# Schematic.net
KiCad netlist of a schematic drawn in Altium Designer
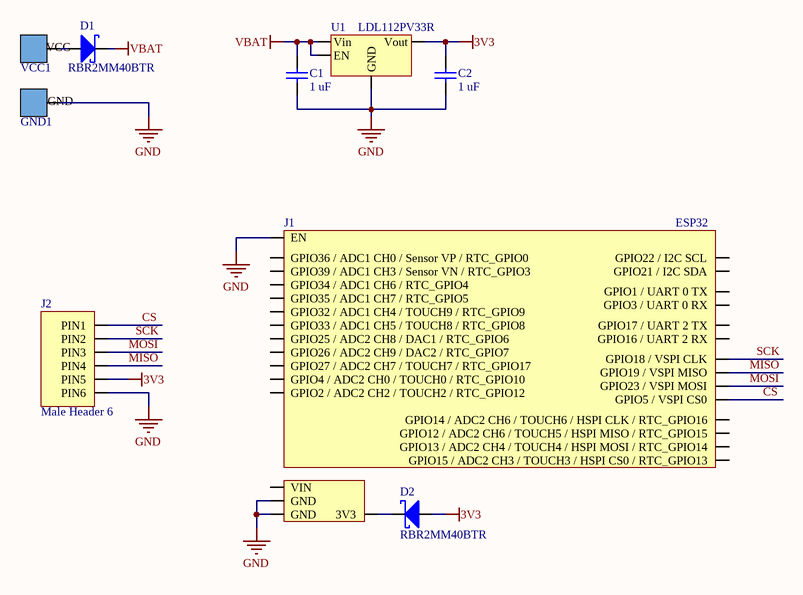
[diagram p0: Schematic.SchDoc]

(export (version "E")
  (design (tool "Eeschema 10.0.6"))
  (components
    (comp (ref "C1")
      (value "1 uF")
      (footprint "C0603")
      (description "CAP CER 1uF 35V X5R 0603")
      (fields
        (field (name "MANUFACTURER") "TAIYO YUDEN")
        (field (name "PART NUMBER") "GMK107BJ105KAHT")
        (field (name "LIBRARY CONTROL - PERSON THAT CHECKED FOOTPRINT") "Nikaum")
        (field (name "LIBRARY CONTROL - PERSON THAT CHECKED SCHEMATIC") "Nikaum")
        (field (name "LIBRARY CONTROL - PERSON THAT DID THE LAST UPDATE FOOTPRINT") "Nikaum")
        (field (name "LIBRARY CONTROL - PERSON THAT DID THE LAST UPDATE SCHEMATIC") "Nikaum")
      )
      (libsource (lib "Uai!Tecas") (part "GMK107BJ105KAHT"))
    )
    (comp (ref "C2")
      (value "1 uF")
      (footprint "C0603")
      (description "CAP CER 1uF 35V X5R 0603")
      (fields
        (field (name "MANUFACTURER") "TAIYO YUDEN")
        (field (name "PART NUMBER") "GMK107BJ105KAHT")
        (field (name "LIBRARY CONTROL - PERSON THAT CHECKED FOOTPRINT") "Nikaum")
        (field (name "LIBRARY CONTROL - PERSON THAT CHECKED SCHEMATIC") "Nikaum")
        (field (name "LIBRARY CONTROL - PERSON THAT DID THE LAST UPDATE FOOTPRINT") "Nikaum")
        (field (name "LIBRARY CONTROL - PERSON THAT DID THE LAST UPDATE SCHEMATIC") "Nikaum")
      )
      (libsource (lib "Uai!Tecas") (part "GMK107BJ105KAHT"))
    )
    (comp (ref "D1")
      (value "RBR2MM40BTR")
      (footprint "DIODO_SOD-123FL-2")
      (description "DIODE SCHOTTKY 40V 2A SOD-123FL-2")
      (fields
        (field (name "MANUFACTURER") "ROHM Semiconductor")
        (field (name "LIBRARY CONTROL - PERSON THAT DID THE LAST UPDATE SCHEMATIC") "Maria Laura")
      )
      (libsource (lib "Uai!Tecas") (part "RBR2MM40BTR"))
    )
    (comp (ref "D2")
      (value "RBR2MM40BTR")
      (footprint "DIODO_SOD-123FL-2")
      (description "DIODE SCHOTTKY 40V 2A SOD-123FL-2")
      (fields
        (field (name "MANUFACTURER") "ROHM Semiconductor")
        (field (name "LIBRARY CONTROL - PERSON THAT DID THE LAST UPDATE SCHEMATIC") "Maria Laura")
      )
      (libsource (lib "Uai!Tecas") (part "RBR2MM40BTR"))
    )
    (comp (ref "GND1")
      (value "Ground Pad")
      (footprint "PAD_ALIMENTAÇÃO_MINI")
      (description "GND PAD MINI SUMÔ")
      (libsource (lib "Uai!Tecas") (part "Ground Pad Mini Sumô"))
    )
    (comp (ref "J1")
      (value "ESP32")
      (footprint "Modulo ESP32")
      (description "Header Modulo ESP32")
      (fields
        (field (name "LIBRARY CONTROL - CHECKED FOOTPRINT") "Nikaum")
        (field (name "LIBRARY CONTROL - CHECKED SCHEMATIC") "Nikaum")
        (field (name "LIBRARY CONTROL - PERSON THAT DID THE LAST UPDATE SCHEMATIC") "Nikaum")
        (field (name "LIBRARY CONTROL - PERSONT THAT DID THE LAST UPDATE FOOTPRINT") "Nikaum")
      )
      (libsource (lib "Uai!Tecas") (part "Modulo ESP32"))
    )
    (comp (ref "J2")
      (value "Male Header 6")
      (footprint "MALE HEADER 6")
      (fields
        (field (name "LIBRARY CONTROL - PERSON THAT CHECKED FOOTPRINT") "Cage")
        (field (name "LIBRARY CONTROL - PERSON THAT CHECKED SCHEMATIC") "Cage")
        (field (name "LIBRARY CONTROL - PERSON THAT DID THE LAST UPDATE SCHEMATIC") "Cage")
        (field (name "LIBRARY CONTROL - PERSONT THAT DID THE LAST UPDATE FOOTPRINT") "Cage")
      )
      (libsource (lib "Uai!Tecas") (part "Male Header 6"))
    )
    (comp (ref "U1")
      (value "LDL112PV33R")
      (footprint "DFN-6")
      (description "IC REG LINEAR 5V 200mA SOT-89-4")
      (libsource (lib "Voltage Regulator") (part "LDL112PV33R"))
    )
    (comp (ref "VCC1")
      (value "Source Pad")
      (footprint "PAD_ALIMENTAÇÃO_MINI")
      (description "VCC PAD MINI SUMÔ")
      (libsource (lib "Uai!Tecas") (part "Source Pad Mini Sumô"))
    )
  )
  (nets
    (net (code "1") (name "/CS") (class "Default")
      (node (ref "J1") (pin "PIN23") (pinfunction "GPIO5_/_VSPI_CS0_PIN23") (pintype "passive"))
      (node (ref "J2") (pin "PIN1") (pinfunction "PIN1_PIN1") (pintype "passive"))
    )
    (net (code "2") (name "/MISO") (class "Default")
      (node (ref "J1") (pin "PIN21") (pinfunction "GPIO19_/_VSPI_MISO_PIN21") (pintype "passive"))
      (node (ref "J2") (pin "PIN4") (pinfunction "PIN4_PIN4") (pintype "passive"))
    )
    (net (code "3") (name "/MOSI") (class "Default")
      (node (ref "J1") (pin "PIN16") (pinfunction "GPIO23_/_VSPI_MOSI_PIN16") (pintype "passive"))
      (node (ref "J2") (pin "PIN3") (pinfunction "PIN3_PIN3") (pintype "passive"))
    )
    (net (code "4") (name "/SCK") (class "Default")
      (node (ref "J1") (pin "PIN22") (pinfunction "GPIO18_/_VSPI_CLK_PIN22") (pintype "passive"))
      (node (ref "J2") (pin "PIN2") (pinfunction "PIN2_PIN2") (pintype "passive"))
    )
    (net (code "5") (name "3V3") (class "Default")
      (node (ref "C2") (pin "2") (pinfunction "2_2") (pintype "passive"))
      (node (ref "D2") (pin "A") (pinfunction "A_A") (pintype "passive"))
      (node (ref "J2") (pin "PIN5") (pinfunction "PIN5_PIN5") (pintype "passive"))
      (node (ref "U1") (pin "4") (pinfunction "Vout_4") (pintype "passive"))
    )
    (net (code "6") (name "GND") (class "Default")
      (node (ref "C1") (pin "1") (pinfunction "1_1") (pintype "passive"))
      (node (ref "C2") (pin "1") (pinfunction "1_1") (pintype "passive"))
      (node (ref "GND1") (pin "A") (pinfunction "GND_A") (pintype "passive"))
      (node (ref "J1") (pin "EN") (pinfunction "EN_EN") (pintype "passive"))
      (node (ref "J1") (pin "GND") (pinfunction "GND_GND") (pintype "passive"))
      (node (ref "J2") (pin "PIN6") (pinfunction "PIN6_PIN6") (pintype "passive"))
      (node (ref "U1") (pin "2") (pinfunction "GND_2") (pintype "passive"))
    )
    (net (code "7") (name "Net-(D2-PadC)") (class "Default")
      (node (ref "D2") (pin "C") (pinfunction "C_C") (pintype "passive"))
      (node (ref "J1") (pin "3V3") (pinfunction "3V3_3V3") (pintype "passive"))
    )
    (net (code "8") (name "Net-(VCC1-VCC)") (class "Default")
      (node (ref "D1") (pin "A") (pinfunction "A_A") (pintype "passive"))
      (node (ref "VCC1") (pin "A") (pinfunction "VCC_A") (pintype "passive"))
    )
    (net (code "9") (name "VBAT") (class "Default")
      (node (ref "C1") (pin "2") (pinfunction "2_2") (pintype "passive"))
      (node (ref "D1") (pin "C") (pinfunction "C_C") (pintype "passive"))
      (node (ref "U1") (pin "1") (pinfunction "EN_1") (pintype "passive"))
      (node (ref "U1") (pin "6") (pinfunction "Vin_6") (pintype "passive"))
    )
    (net (code "10") (name "unconnected-(J1-GPIO1_{slash}_UART_0_TX-PadPIN18)") (class "Default")
      (node (ref "J1") (pin "PIN18") (pinfunction "GPIO1_/_UART_0_TX_PIN18") (pintype "passive"))
    )
    (net (code "11") (name "unconnected-(J1-GPIO2_{slash}_ADC2_CH2_{slash}_TOUCH2_{slash}_RTC_GPIO12-PadPIN27)") (class "Default")
      (node (ref "J1") (pin "PIN27") (pinfunction "GPIO2_/_ADC2_CH2_/_TOUCH2_/_RTC_GPIO12_PIN27") (pintype "passive"))
    )
    (net (code "12") (name "unconnected-(J1-GPIO3_{slash}_UART_0_RX-PadPIN19)") (class "Default")
      (node (ref "J1") (pin "PIN19") (pinfunction "GPIO3_/_UART_0_RX_PIN19") (pintype "passive"))
    )
    (net (code "13") (name "unconnected-(J1-GPIO4_{slash}_ADC2_CH0_{slash}_TOUCH0_{slash}_RTC_GPIO10-PadPIN26)") (class "Default")
      (node (ref "J1") (pin "PIN26") (pinfunction "GPIO4_/_ADC2_CH0_/_TOUCH0_/_RTC_GPIO10_PIN26") (pintype "passive"))
    )
    (net (code "14") (name "unconnected-(J1-GPIO12_{slash}_ADC2_CH6_{slash}_TOUCH5_{slash}_HSPI_MISO_{slash}_RTC_GPIO15-PadPIN12)") (class "Default")
      (node (ref "J1") (pin "PIN12") (pinfunction "GPIO12_/_ADC2_CH6_/_TOUCH5_/_HSPI_MISO_/_RTC_GPIO15_PIN12") (pintype "passive"))
    )
    (net (code "15") (name "unconnected-(J1-GPIO13_{slash}_ADC2_CH4_{slash}_TOUCH4_{slash}_HSPI_MOSI_{slash}_RTC_GPIO14-PadPIN13)") (class "Default")
      (node (ref "J1") (pin "PIN13") (pinfunction "GPIO13_/_ADC2_CH4_/_TOUCH4_/_HSPI_MOSI_/_RTC_GPIO14_PIN13") (pintype "passive"))
    )
    (net (code "16") (name "unconnected-(J1-GPIO14_{slash}_ADC2_CH6_{slash}_TOUCH6_{slash}_HSPI_CLK_{slash}_RTC_GPIO16-PadPIN11)") (class "Default")
      (node (ref "J1") (pin "PIN11") (pinfunction "GPIO14_/_ADC2_CH6_/_TOUCH6_/_HSPI_CLK_/_RTC_GPIO16_PIN11") (pintype "passive"))
    )
    (net (code "17") (name "unconnected-(J1-GPIO15_{slash}_ADC2_CH3_{slash}_TOUCH3_{slash}_HSPI_CS0_{slash}_RTC_GPIO13-PadPIN28)") (class "Default")
      (node (ref "J1") (pin "PIN28") (pinfunction "GPIO15_/_ADC2_CH3_/_TOUCH3_/_HSPI_CS0_/_RTC_GPIO13_PIN28") (pintype "passive"))
    )
    (net (code "18") (name "unconnected-(J1-GPIO16_{slash}_UART_2_RX-PadPIN25)") (class "Default")
      (node (ref "J1") (pin "PIN25") (pinfunction "GPIO16_/_UART_2_RX_PIN25") (pintype "passive"))
    )
    (net (code "19") (name "unconnected-(J1-GPIO17_{slash}_UART_2_TX-PadPIN24)") (class "Default")
      (node (ref "J1") (pin "PIN24") (pinfunction "GPIO17_/_UART_2_TX_PIN24") (pintype "passive"))
    )
    (net (code "20") (name "unconnected-(J1-GPIO21_{slash}_I2C_SDA-PadPIN20)") (class "Default")
      (node (ref "J1") (pin "PIN20") (pinfunction "GPIO21_/_I2C_SDA_PIN20") (pintype "passive"))
    )
    (net (code "21") (name "unconnected-(J1-GPIO22_{slash}_I2C_SCL-PadPIN17)") (class "Default")
      (node (ref "J1") (pin "PIN17") (pinfunction "GPIO22_/_I2C_SCL_PIN17") (pintype "passive"))
    )
    (net (code "22") (name "unconnected-(J1-GPIO25_{slash}_ADC2_CH8_{slash}_DAC1_{slash}_RTC_GPIO6-PadPIN8)") (class "Default")
      (node (ref "J1") (pin "PIN8") (pinfunction "GPIO25_/_ADC2_CH8_/_DAC1_/_RTC_GPIO6_PIN8") (pintype "passive"))
    )
    (net (code "23") (name "unconnected-(J1-GPIO26_{slash}_ADC2_CH9_{slash}_DAC2_{slash}_RTC_GPIO7-PadPIN9)") (class "Default")
      (node (ref "J1") (pin "PIN9") (pinfunction "GPIO26_/_ADC2_CH9_/_DAC2_/_RTC_GPIO7_PIN9") (pintype "passive"))
    )
    (net (code "24") (name "unconnected-(J1-GPIO27_{slash}_ADC2_CH7_{slash}_TOUCH7_{slash}_RTC_GPIO17-PadPIN10)") (class "Default")
      (node (ref "J1") (pin "PIN10") (pinfunction "GPIO27_/_ADC2_CH7_/_TOUCH7_/_RTC_GPIO17_PIN10") (pintype "passive"))
    )
    (net (code "25") (name "unconnected-(J1-GPIO32_{slash}_ADC1_CH4_{slash}_TOUCH9_{slash}_RTC_GPIO9-PadPIN6)") (class "Default")
      (node (ref "J1") (pin "PIN6") (pinfunction "GPIO32_/_ADC1_CH4_/_TOUCH9_/_RTC_GPIO9_PIN6") (pintype "passive"))
    )
    (net (code "26") (name "unconnected-(J1-GPIO33_{slash}_ADC1_CH5_{slash}_TOUCH8_{slash}_RTC_GPIO8-PadPIN7)") (class "Default")
      (node (ref "J1") (pin "PIN7") (pinfunction "GPIO33_/_ADC1_CH5_/_TOUCH8_/_RTC_GPIO8_PIN7") (pintype "passive"))
    )
    (net (code "27") (name "unconnected-(J1-GPIO34_{slash}_ADC1_CH6_{slash}_RTC_GPIO4-PadPIN4)") (class "Default")
      (node (ref "J1") (pin "PIN4") (pinfunction "GPIO34_/_ADC1_CH6_/_RTC_GPIO4_PIN4") (pintype "passive"))
    )
    (net (code "28") (name "unconnected-(J1-GPIO35_{slash}_ADC1_CH7_{slash}_RTC_GPIO5-PadPIN5)") (class "Default")
      (node (ref "J1") (pin "PIN5") (pinfunction "GPIO35_/_ADC1_CH7_/_RTC_GPIO5_PIN5") (pintype "passive"))
    )
    (net (code "29") (name "unconnected-(J1-GPIO36_{slash}_ADC1_CH0_{slash}_Sensor_VP_{slash}_RTC_GPIO0-PadPIN2)") (class "Default")
      (node (ref "J1") (pin "PIN2") (pinfunction "GPIO36_/_ADC1_CH0_/_Sensor_VP_/_RTC_GPIO0_PIN2") (pintype "passive"))
    )
    (net (code "30") (name "unconnected-(J1-GPIO39_{slash}_ADC1_CH3_{slash}_Sensor_VN_{slash}_RTC_GPIO3-PadPIN3)") (class "Default")
      (node (ref "J1") (pin "PIN3") (pinfunction "GPIO39_/_ADC1_CH3_/_Sensor_VN_/_RTC_GPIO3_PIN3") (pintype "passive"))
    )
    (net (code "31") (name "unconnected-(J1-PadVIN)") (class "Default")
      (node (ref "J1") (pin "VIN") (pinfunction "VIN_VIN") (pintype "passive"))
    )
  )
)
